# MB1297_Peripherals.net
KiCad netlist of a schematic drawn in Altium Designer
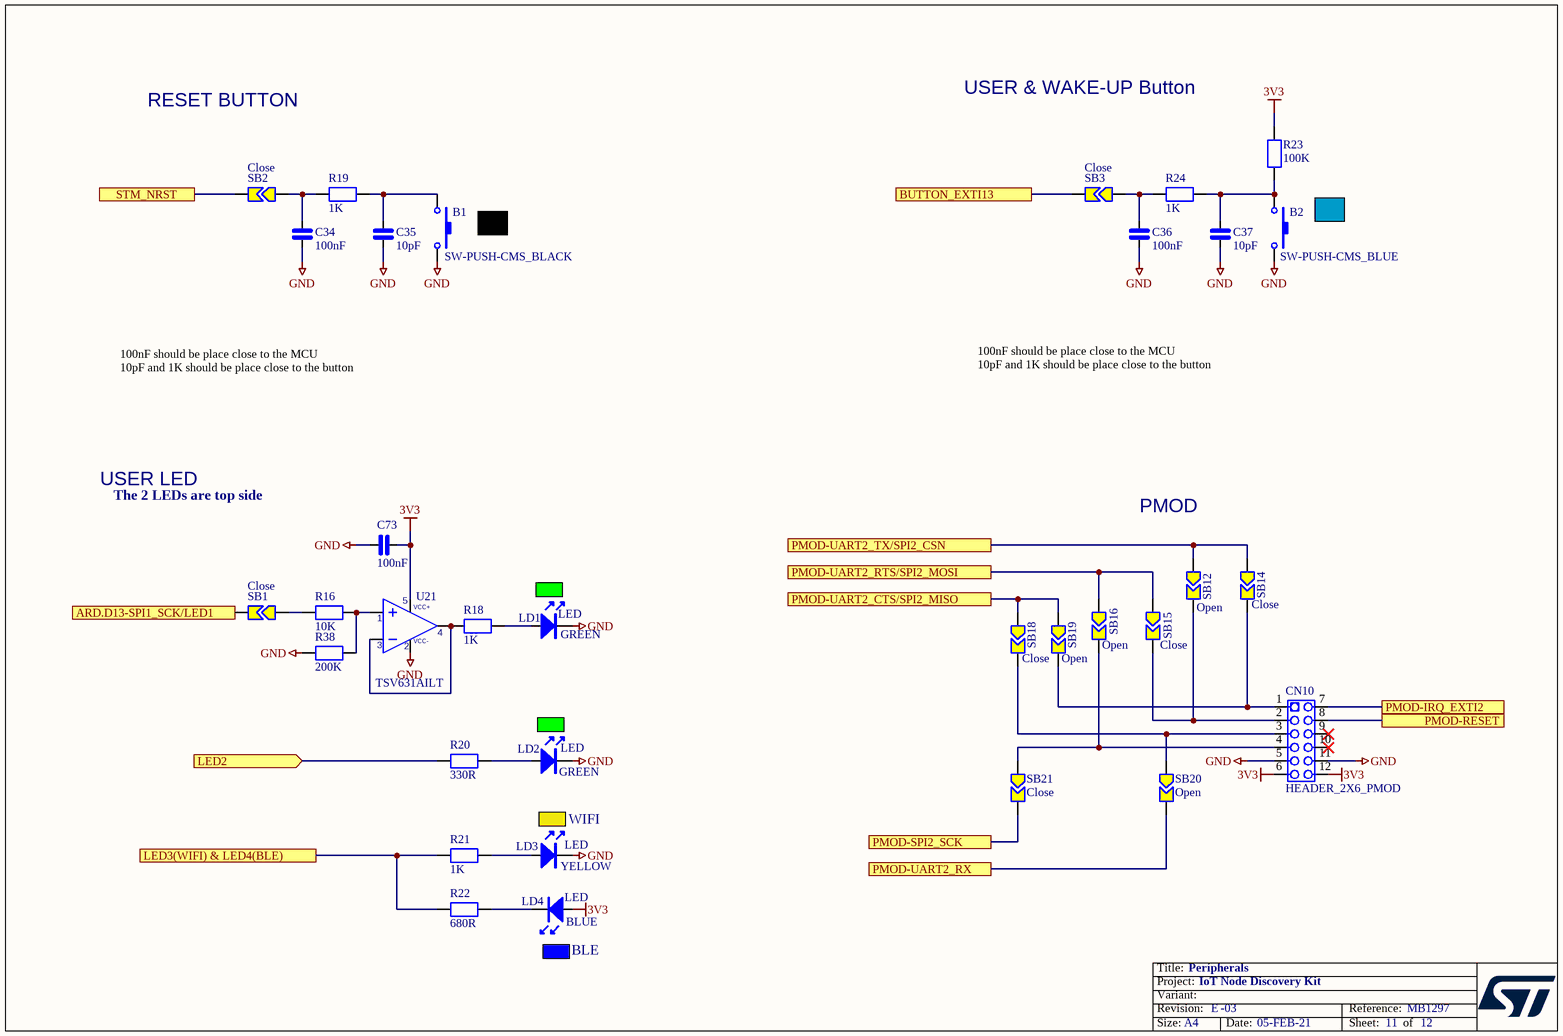
[diagram p0: MB1297_Peripherals.SchDoc]

(export (version "E")
  (design (tool "Eeschema 10.0.6"))
  (components
    (comp (ref "B1")
      (value "SW-PUSH-CMS_BLACK")
      (footprint "SWI_WEALTHMETAL_TD-0341_4P - BACK")
      (description "Push-button SMD")
      (libsource (lib "ST_Lib3D") (part "SW-PB_2"))
    )
    (comp (ref "B2")
      (value "SW-PUSH-CMS_BLUE")
      (footprint "SWI_WEALTHMETAL_TD-0341_4P - BLUE")
      (description "Push-button SMD")
      (libsource (lib "ST_Lib3D") (part "SW-PB_2"))
    )
    (comp (ref "C34")
      (value "100nF")
      (footprint "0402")
      (description "Capacitor_not polarized")
      (libsource (lib "ST_Lib3D") (part "CAP_NPOL"))
    )
    (comp (ref "C35")
      (value "10pF")
      (footprint "0402")
      (description "Capacitor_not polarized")
      (libsource (lib "ST_Lib3D") (part "CAP_NPOL"))
    )
    (comp (ref "C36")
      (value "100nF")
      (footprint "0402")
      (description "Capacitor_not polarized")
      (libsource (lib "ST_Lib3D") (part "CAP_NPOL"))
    )
    (comp (ref "C37")
      (value "10pF")
      (footprint "0402")
      (description "Capacitor_not polarized")
      (libsource (lib "ST_Lib3D") (part "CAP_NPOL"))
    )
    (comp (ref "C73")
      (value "100nF")
      (footprint "0402")
      (description "Capacitor_not polarized")
      (libsource (lib "ST_Lib3D") (part "CAP_NPOL"))
    )
    (comp (ref "CN10")
      (value "HEADER_2X6_PMOD")
      (footprint "Header F 2x6x2.54 TH H PMOD")
      (description "PMOD Connector Warning Specific Pinout")
      (libsource (lib "ST_Lib3D") (part "HEADER_2X6_PMOD"))
    )
    (comp (ref "LD1")
      (value "LED")
      (footprint "0603_LED_GREEN")
      (description "Light-Emitting Diode")
      (fields (field (name "COLOR") "GREEN"))
      (libsource (lib "ST_Lib3D") (part "LED"))
    )
    (comp (ref "LD2")
      (value "LED")
      (footprint "0603_LED_GREEN")
      (description "Light-Emitting Diode")
      (fields (field (name "COLOR") "GREEN"))
      (libsource (lib "ST_Lib3D") (part "LED"))
    )
    (comp (ref "LD3")
      (value "LED")
      (footprint "0603_LED_Yellow")
      (description "Light-Emitting Diode")
      (fields (field (name "COLOR") "YELLOW"))
      (libsource (lib "ST_Lib3D") (part "LED"))
    )
    (comp (ref "LD4")
      (value "LED")
      (footprint "0603_LED_Blue")
      (description "Light-Emitting Diode")
      (fields (field (name "COLOR") "BLUE"))
      (libsource (lib "ST_Lib3D") (part "LED"))
    )
    (comp (ref "R16")
      (value "10K")
      (footprint "0402")
      (description "Resistor")
      (libsource (lib "Lib3D_Altium10_Schlib") (part "RES"))
    )
    (comp (ref "R18")
      (value "1K")
      (footprint "0402")
      (description "Resistor")
      (libsource (lib "Lib3D_Altium10_Schlib") (part "RES"))
    )
    (comp (ref "R19")
      (value "1K")
      (footprint "0402")
      (description "Resistor")
      (libsource (lib "Lib3D_Altium10_Schlib") (part "RES"))
    )
    (comp (ref "R20")
      (value "330R")
      (footprint "0402")
      (description "Resistor")
      (libsource (lib "Lib3D_Altium10_Schlib") (part "RES"))
    )
    (comp (ref "R21")
      (value "1K")
      (footprint "0402")
      (description "Resistor")
      (libsource (lib "Lib3D_Altium10_Schlib") (part "RES"))
    )
    (comp (ref "R22")
      (value "680R")
      (footprint "0402")
      (description "Resistor")
      (libsource (lib "Lib3D_Altium10_Schlib") (part "RES"))
    )
    (comp (ref "R23")
      (value "100K")
      (footprint "0402")
      (description "Resistor")
      (libsource (lib "Lib3D_Altium10_Schlib") (part "RES"))
    )
    (comp (ref "R24")
      (value "1K")
      (footprint "0402")
      (description "Resistor")
      (libsource (lib "Lib3D_Altium10_Schlib") (part "RES"))
    )
    (comp (ref "R38")
      (value "200K")
      (footprint "0402")
      (description "Resistor")
      (libsource (lib "Lib3D_Altium10_Schlib") (part "RES"))
    )
    (comp (ref "SB1")
      (value "Close")
      (footprint "SB")
      (description "Solder Jumper")
      (fields (field (name "PUBLISHER") "Altium Limited"))
      (libsource (lib "Lib3D_Altium10_Schlib") (part "Strap2"))
    )
    (comp (ref "SB2")
      (value "Close")
      (footprint "SB")
      (description "Solder Jumper")
      (fields (field (name "PUBLISHER") "Altium Limited"))
      (libsource (lib "Lib3D_Altium10_Schlib") (part "Strap2"))
    )
    (comp (ref "SB3")
      (value "Close")
      (footprint "SB")
      (description "Solder Jumper")
      (fields (field (name "PUBLISHER") "Altium Limited"))
      (libsource (lib "Lib3D_Altium10_Schlib") (part "Strap2"))
    )
    (comp (ref "SB12")
      (value "Open")
      (footprint "SB")
      (description "Solder Jumper")
      (fields (field (name "PUBLISHER") "Altium Limited"))
      (libsource (lib "Lib3D_Altium10_Schlib") (part "Strap2"))
    )
    (comp (ref "SB14")
      (value "Close")
      (footprint "SB")
      (description "Solder Jumper")
      (fields (field (name "PUBLISHER") "Altium Limited"))
      (libsource (lib "Lib3D_Altium10_Schlib") (part "Strap2"))
    )
    (comp (ref "SB15")
      (value "Close")
      (footprint "SB")
      (description "Solder Jumper")
      (fields (field (name "PUBLISHER") "Altium Limited"))
      (libsource (lib "Lib3D_Altium10_Schlib") (part "Strap2"))
    )
    (comp (ref "SB16")
      (value "Open")
      (footprint "SB")
      (description "Solder Jumper")
      (fields (field (name "PUBLISHER") "Altium Limited"))
      (libsource (lib "Lib3D_Altium10_Schlib") (part "Strap2"))
    )
    (comp (ref "SB18")
      (value "Close")
      (footprint "SB")
      (description "Solder Jumper")
      (fields (field (name "PUBLISHER") "Altium Limited"))
      (libsource (lib "Lib3D_Altium10_Schlib") (part "Strap2"))
    )
    (comp (ref "SB19")
      (value "Open")
      (footprint "SB")
      (description "Solder Jumper")
      (fields (field (name "PUBLISHER") "Altium Limited"))
      (libsource (lib "Lib3D_Altium10_Schlib") (part "Strap2"))
    )
    (comp (ref "SB20")
      (value "Open")
      (footprint "SB")
      (description "Solder Jumper")
      (fields (field (name "PUBLISHER") "Altium Limited"))
      (libsource (lib "Lib3D_Altium10_Schlib") (part "Strap2"))
    )
    (comp (ref "SB21")
      (value "Close")
      (footprint "SB")
      (description "Solder Jumper")
      (fields (field (name "PUBLISHER") "Altium Limited"))
      (libsource (lib "Lib3D_Altium10_Schlib") (part "Strap2"))
    )
    (comp (ref "U21")
      (value "TSV631AILT")
      (footprint "ST_Lib3D:SOT23-5")
      (description "TSV631AILT  Rail-to-rail input/output, 60 µA, 880 kHz, 5 V CMOS  operational amplifiers")
      (libsource (lib "ST_Lib3D") (part "TSV631AILT"))
    )
  )
  (nets
    (net (code "1") (name "/ARD.D13-SPI1_SCK{slash}LED1") (class "Default")
      (node (ref "SB1") (pin "1") (pinfunction "1_1") (pintype "passive"))
    )
    (net (code "2") (name "/BUTTON_EXTI13") (class "Default")
      (node (ref "SB3") (pin "1") (pinfunction "1_1") (pintype "passive"))
    )
    (net (code "3") (name "/LED2") (class "Default")
      (node (ref "R20") (pin "1") (pinfunction "1_1") (pintype "passive"))
    )
    (net (code "4") (name "/LED3(WIFI) & LED4(BLE)") (class "Default")
      (node (ref "R21") (pin "1") (pinfunction "1_1") (pintype "passive"))
      (node (ref "R22") (pin "1") (pinfunction "1_1") (pintype "passive"))
    )
    (net (code "5") (name "/PMOD-IRQ_EXTI2") (class "Default")
      (node (ref "CN10") (pin "7") (pinfunction "7_7") (pintype "passive"))
    )
    (net (code "6") (name "/PMOD-RESET") (class "Default")
      (node (ref "CN10") (pin "8") (pinfunction "8_8") (pintype "passive"))
    )
    (net (code "7") (name "/PMOD-SPI2_SCK") (class "Default")
      (node (ref "SB21") (pin "1") (pinfunction "1_1") (pintype "passive"))
    )
    (net (code "8") (name "/PMOD-UART2_CTS{slash}SPI2_MISO") (class "Default")
      (node (ref "SB18") (pin "2") (pinfunction "2_2") (pintype "passive"))
      (node (ref "SB19") (pin "2") (pinfunction "2_2") (pintype "passive"))
    )
    (net (code "9") (name "/PMOD-UART2_RTS{slash}SPI2_MOSI") (class "Default")
      (node (ref "SB15") (pin "2") (pinfunction "2_2") (pintype "passive"))
      (node (ref "SB16") (pin "2") (pinfunction "2_2") (pintype "passive"))
    )
    (net (code "10") (name "/PMOD-UART2_RX") (class "Default")
      (node (ref "SB20") (pin "1") (pinfunction "1_1") (pintype "passive"))
    )
    (net (code "11") (name "/PMOD-UART2_TX{slash}SPI2_CSN") (class "Default")
      (node (ref "SB12") (pin "2") (pinfunction "2_2") (pintype "passive"))
      (node (ref "SB14") (pin "2") (pinfunction "2_2") (pintype "passive"))
    )
    (net (code "12") (name "/STM_NRST") (class "Default")
      (node (ref "SB2") (pin "1") (pinfunction "1_1") (pintype "passive"))
    )
    (net (code "13") (name "3V3") (class "Default")
      (node (ref "C73") (pin "1") (pinfunction "1_1") (pintype "passive"))
      (node (ref "CN10") (pin "12") (pinfunction "12_12") (pintype "passive"))
      (node (ref "CN10") (pin "6") (pinfunction "6_6") (pintype "passive"))
      (node (ref "LD4") (pin "A") (pinfunction "A_A") (pintype "passive"))
      (node (ref "R23") (pin "2") (pinfunction "2_2") (pintype "passive"))
      (node (ref "U21") (pin "5") (pinfunction "V+_5") (pintype "passive"))
    )
    (net (code "14") (name "GND") (class "Default")
      (node (ref "B1") (pin "2") (pinfunction "2_2") (pintype "passive"))
      (node (ref "B2") (pin "2") (pinfunction "2_2") (pintype "passive"))
      (node (ref "C34") (pin "2") (pinfunction "2_2") (pintype "passive"))
      (node (ref "C35") (pin "2") (pinfunction "2_2") (pintype "passive"))
      (node (ref "C36") (pin "2") (pinfunction "2_2") (pintype "passive"))
      (node (ref "C37") (pin "2") (pinfunction "2_2") (pintype "passive"))
      (node (ref "C73") (pin "2") (pinfunction "2_2") (pintype "passive"))
      (node (ref "CN10") (pin "11") (pinfunction "11_11") (pintype "passive"))
      (node (ref "CN10") (pin "5") (pinfunction "5_5") (pintype "passive"))
      (node (ref "LD1") (pin "K") (pinfunction "K_K") (pintype "passive"))
      (node (ref "LD2") (pin "K") (pinfunction "K_K") (pintype "passive"))
      (node (ref "LD3") (pin "K") (pinfunction "K_K") (pintype "passive"))
      (node (ref "R38") (pin "1") (pinfunction "1_1") (pintype "passive"))
      (node (ref "U21") (pin "2") (pinfunction "V-_2") (pintype "passive"))
    )
    (net (code "15") (name "Net-(B1-Pad1)") (class "Default")
      (node (ref "B1") (pin "1") (pinfunction "1_1") (pintype "passive"))
      (node (ref "C35") (pin "1") (pinfunction "1_1") (pintype "passive"))
      (node (ref "R19") (pin "2") (pinfunction "2_2") (pintype "passive"))
    )
    (net (code "16") (name "Net-(B2-Pad1)") (class "Default")
      (node (ref "B2") (pin "1") (pinfunction "1_1") (pintype "passive"))
      (node (ref "C37") (pin "1") (pinfunction "1_1") (pintype "passive"))
      (node (ref "R23") (pin "1") (pinfunction "1_1") (pintype "passive"))
      (node (ref "R24") (pin "2") (pinfunction "2_2") (pintype "passive"))
    )
    (net (code "17") (name "Net-(C34-Pad1)") (class "Default")
      (node (ref "C34") (pin "1") (pinfunction "1_1") (pintype "passive"))
      (node (ref "R19") (pin "1") (pinfunction "1_1") (pintype "passive"))
      (node (ref "SB2") (pin "2") (pinfunction "2_2") (pintype "passive"))
    )
    (net (code "18") (name "Net-(C36-Pad1)") (class "Default")
      (node (ref "C36") (pin "1") (pinfunction "1_1") (pintype "passive"))
      (node (ref "R24") (pin "1") (pinfunction "1_1") (pintype "passive"))
      (node (ref "SB3") (pin "2") (pinfunction "2_2") (pintype "passive"))
    )
    (net (code "19") (name "Net-(CN10-Pad1)") (class "Default")
      (node (ref "CN10") (pin "1") (pinfunction "1_1") (pintype "passive"))
      (node (ref "SB14") (pin "1") (pinfunction "1_1") (pintype "passive"))
      (node (ref "SB19") (pin "1") (pinfunction "1_1") (pintype "passive"))
    )
    (net (code "20") (name "Net-(CN10-Pad2)") (class "Default")
      (node (ref "CN10") (pin "2") (pinfunction "2_2") (pintype "passive"))
      (node (ref "SB12") (pin "1") (pinfunction "1_1") (pintype "passive"))
      (node (ref "SB15") (pin "1") (pinfunction "1_1") (pintype "passive"))
    )
    (net (code "21") (name "Net-(CN10-Pad3)") (class "Default")
      (node (ref "CN10") (pin "3") (pinfunction "3_3") (pintype "passive"))
      (node (ref "SB18") (pin "1") (pinfunction "1_1") (pintype "passive"))
      (node (ref "SB20") (pin "2") (pinfunction "2_2") (pintype "passive"))
    )
    (net (code "22") (name "Net-(CN10-Pad4)") (class "Default")
      (node (ref "CN10") (pin "4") (pinfunction "4_4") (pintype "passive"))
      (node (ref "SB16") (pin "1") (pinfunction "1_1") (pintype "passive"))
      (node (ref "SB21") (pin "2") (pinfunction "2_2") (pintype "passive"))
    )
    (net (code "23") (name "Net-(LD1-PadA)") (class "Default")
      (node (ref "LD1") (pin "A") (pinfunction "A_A") (pintype "passive"))
      (node (ref "R18") (pin "2") (pinfunction "2_2") (pintype "passive"))
    )
    (net (code "24") (name "Net-(LD2-PadA)") (class "Default")
      (node (ref "LD2") (pin "A") (pinfunction "A_A") (pintype "passive"))
      (node (ref "R20") (pin "2") (pinfunction "2_2") (pintype "passive"))
    )
    (net (code "25") (name "Net-(LD3-PadA)") (class "Default")
      (node (ref "LD3") (pin "A") (pinfunction "A_A") (pintype "passive"))
      (node (ref "R21") (pin "2") (pinfunction "2_2") (pintype "passive"))
    )
    (net (code "26") (name "Net-(LD4-PadK)") (class "Default")
      (node (ref "LD4") (pin "K") (pinfunction "K_K") (pintype "passive"))
      (node (ref "R22") (pin "2") (pinfunction "2_2") (pintype "passive"))
    )
    (net (code "27") (name "Net-(R16-Pad1)") (class "Default")
      (node (ref "R16") (pin "1") (pinfunction "1_1") (pintype "passive"))
      (node (ref "SB1") (pin "2") (pinfunction "2_2") (pintype "passive"))
    )
    (net (code "28") (name "Net-(U21-IN+)") (class "Default")
      (node (ref "R16") (pin "2") (pinfunction "2_2") (pintype "passive"))
      (node (ref "R38") (pin "2") (pinfunction "2_2") (pintype "passive"))
      (node (ref "U21") (pin "1") (pinfunction "IN+_1") (pintype "passive"))
    )
    (net (code "29") (name "Net-(U21-IN-)") (class "Default")
      (node (ref "R18") (pin "1") (pinfunction "1_1") (pintype "passive"))
      (node (ref "U21") (pin "3") (pinfunction "IN-_3") (pintype "passive"))
      (node (ref "U21") (pin "4") (pinfunction "OUT_4") (pintype "passive"))
    )
    (net (code "30") (name "unconnected-(CN10-Pad9)") (class "Default")
      (node (ref "CN10") (pin "9") (pinfunction "9_9") (pintype "passive+no_connect"))
    )
    (net (code "31") (name "unconnected-(CN10-Pad10)") (class "Default")
      (node (ref "CN10") (pin "10") (pinfunction "10_10") (pintype "passive+no_connect"))
    )
  )
)
